# TMC2130.net
KiCad netlist of a schematic drawn in Altium Designer
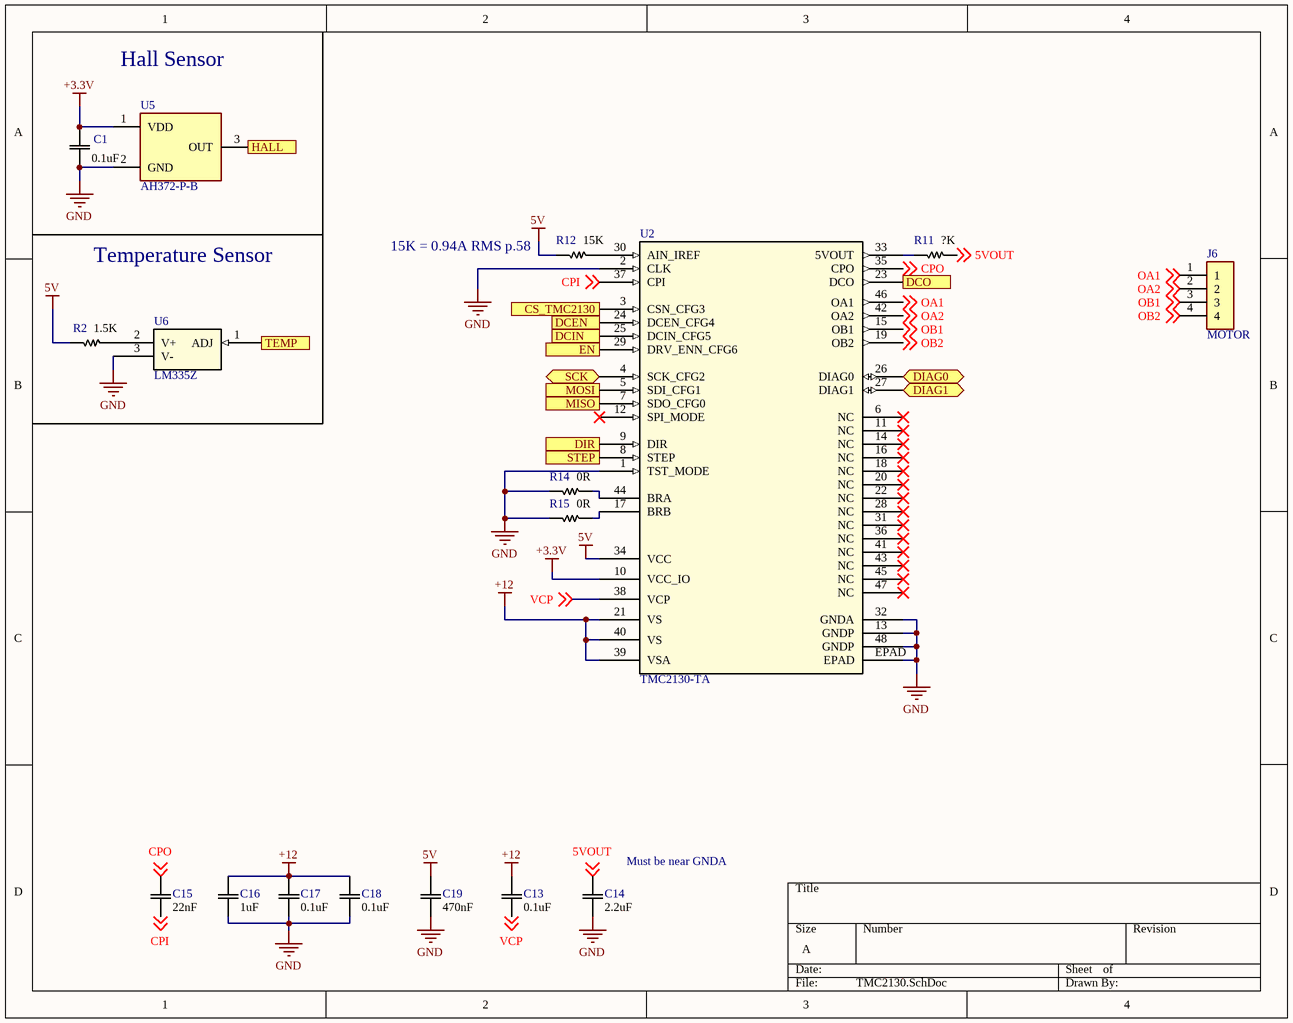
[diagram p0: TMC2130.SchDoc]

(export (version "E")
  (design (tool "Eeschema 10.0.6"))
  (components
    (comp (ref "C1")
      (value "0.1uF")
      (footprint "0603")
      (description "Capacitor SMD 1206")
      (fields
        (field (name "MANUFACTURER_PART_NUMBER") "12065A820JAT2A")
        (field (name "Comment") "Capacitor 1206")
        (field (name "COPYRIGHT") "Copyright (C) 2018 Accelerated Designs. All rights reserved")
      )
      (libsource (lib "Schematic_Emile") (part "Capacitor 1206"))
    )
    (comp (ref "C13")
      (value "0.1uF")
      (footprint "0603")
      (description "Capacitor SMD 1206")
      (fields
        (field (name "MANUFACTURER_PART_NUMBER") "12065A820JAT2A")
        (field (name "Comment") "Capacitor 1206")
        (field (name "COPYRIGHT") "Copyright (C) 2018 Accelerated Designs. All rights reserved")
      )
      (libsource (lib "Schematic_Emile") (part "Capacitor 1206"))
    )
    (comp (ref "C14")
      (value "2.2uF")
      (footprint "0603")
      (description "Capacitor SMD 1206")
      (fields
        (field (name "MANUFACTURER_PART_NUMBER") "12065A820JAT2A")
        (field (name "Comment") "Capacitor 1206")
        (field (name "COPYRIGHT") "Copyright (C) 2018 Accelerated Designs. All rights reserved")
      )
      (libsource (lib "Schematic_Emile") (part "Capacitor 1206"))
    )
    (comp (ref "C15")
      (value "22nF")
      (footprint "0603")
      (description "Capacitor SMD 1206")
      (fields
        (field (name "MANUFACTURER_PART_NUMBER") "12065A820JAT2A")
        (field (name "Comment") "Capacitor 1206")
        (field (name "COPYRIGHT") "Copyright (C) 2018 Accelerated Designs. All rights reserved")
      )
      (libsource (lib "Schematic_Emile") (part "Capacitor 1206"))
    )
    (comp (ref "C16")
      (value "1uF")
      (footprint "0603")
      (description "Capacitor SMD 1206")
      (fields
        (field (name "MANUFACTURER_PART_NUMBER") "12065A820JAT2A")
        (field (name "Comment") "Capacitor 1206")
        (field (name "COPYRIGHT") "Copyright (C) 2018 Accelerated Designs. All rights reserved")
      )
      (libsource (lib "Schematic_Emile") (part "Capacitor 1206"))
    )
    (comp (ref "C17")
      (value "0.1uF")
      (footprint "0603")
      (description "Capacitor SMD 1206")
      (fields
        (field (name "MANUFACTURER_PART_NUMBER") "12065A820JAT2A")
        (field (name "Comment") "Capacitor 1206")
        (field (name "COPYRIGHT") "Copyright (C) 2018 Accelerated Designs. All rights reserved")
      )
      (libsource (lib "Schematic_Emile") (part "Capacitor 1206"))
    )
    (comp (ref "C18")
      (value "0.1uF")
      (footprint "0603")
      (description "Capacitor SMD 1206")
      (fields
        (field (name "MANUFACTURER_PART_NUMBER") "12065A820JAT2A")
        (field (name "Comment") "Capacitor 1206")
        (field (name "COPYRIGHT") "Copyright (C) 2018 Accelerated Designs. All rights reserved")
      )
      (libsource (lib "Schematic_Emile") (part "Capacitor 1206"))
    )
    (comp (ref "C19")
      (value "470nF")
      (footprint "0603")
      (description "Capacitor SMD 1206")
      (fields
        (field (name "MANUFACTURER_PART_NUMBER") "12065A820JAT2A")
        (field (name "Comment") "Capacitor 1206")
        (field (name "COPYRIGHT") "Copyright (C) 2018 Accelerated Designs. All rights reserved")
      )
      (libsource (lib "Schematic_Emile") (part "Capacitor 1206"))
    )
    (comp (ref "J6")
      (value "MOTOR")
      (footprint "JST 4POS 2.5mm 90°")
      (description "Connector")
      (fields
        (field (name "MANUFACTURER_PART_NUMBER") "S4B-XH-A(LF)(SN)")
        (field (name "RS PART NUMBER") "8201589P")
      )
      (libsource (lib "Schematic_Emile") (part "JST 4POS"))
    )
    (comp (ref "R2")
      (value "1.5K")
      (footprint "0603")
      (description "Resistor 1206 SMD")
      (fields
        (field (name "MANUFACTURER_PART_NUMBER") "ERJ8CWFR024V")
        (field (name "Comment") "Resistor 1206")
        (field (name "COPYRIGHT") "Copyright (C) 2018 Accelerated Designs. All rights reserved")
      )
      (libsource (lib "Schematic_Emile") (part "Resistor 1206"))
    )
    (comp (ref "R11")
      (value "?K")
      (footprint "0603")
      (description "Resistor 0603 SMD")
      (fields
        (field (name "MANUFACTURER_PART_NUMBER") "ERJ8CWFR024V")
        (field (name "Comment") "Resistor 0603")
        (field (name "COPYRIGHT") "Copyright (C) 2018 Accelerated Designs. All rights reserved")
      )
      (libsource (lib "Schematic_Emile") (part "Resistor 1206"))
    )
    (comp (ref "R12")
      (value "15K")
      (footprint "0603")
      (description "Resistor 0603 SMD")
      (fields
        (field (name "MANUFACTURER_PART_NUMBER") "ERJ8CWFR024V")
        (field (name "Comment") "Resistor 0603")
        (field (name "COPYRIGHT") "Copyright (C) 2018 Accelerated Designs. All rights reserved")
      )
      (libsource (lib "Schematic_Emile") (part "Resistor 1206"))
    )
    (comp (ref "R14")
      (value "0R")
      (footprint "0603")
      (description "Resistor 0603 SMD")
      (fields
        (field (name "MANUFACTURER_PART_NUMBER") "ERJ8CWFR024V")
        (field (name "Comment") "Resistor 0603")
        (field (name "COPYRIGHT") "Copyright (C) 2018 Accelerated Designs. All rights reserved")
      )
      (libsource (lib "Schematic_Emile") (part "Resistor 1206"))
    )
    (comp (ref "R15")
      (value "0R")
      (footprint "0603")
      (description "Resistor 0603 SMD")
      (fields
        (field (name "MANUFACTURER_PART_NUMBER") "ERJ8CWFR024V")
        (field (name "Comment") "Resistor 0603")
        (field (name "COPYRIGHT") "Copyright (C) 2018 Accelerated Designs. All rights reserved")
      )
      (libsource (lib "Schematic_Emile") (part "Resistor 1206"))
    )
    (comp (ref "U2")
      (value "TMC2130-TA")
      (footprint "eTQFP48_9x9")
      (description "Motor Driver TMC2130")
      (fields (field (name "COPYRIGHT") "Copyright (C) 2016 Accelerated Designs. All rights reserved"))
      (libsource (lib "Schematic_Emile") (part "TMC2130-TA"))
    )
    (comp (ref "U5")
      (value "AH372-P-B")
      (footprint "Footprint_Emile:AH372PB")
      (description "Hall Sensor")
      (fields (field (name "MOUSER PART NUMBER") "621-AH372-P-B") (field (name "RS PART NUMBER") "1333361P"))
      (libsource (lib "Schematic_Emile") (part "AH372-P-B"))
    )
    (comp (ref "U6")
      (value "LM335Z")
      (footprint "TO92")
      (description "Temperature Sensor")
      (fields (field (name "COPYRIGHT") "Copyright (C) 2018 Accelerated Designs. All rights reserved"))
      (libsource (lib "Schematic_Emile") (part "LM335Z"))
    )
  )
  (nets
    (net (code "1") (name "+3.3V") (class "Default")
      (node (ref "C1") (pin "2") (pinfunction "2_2") (pintype "passive"))
      (node (ref "U2") (pin "10") (pinfunction "VCC_IO_10") (pintype "power_in"))
      (node (ref "U5") (pin "1") (pinfunction "VDD_1") (pintype "passive"))
    )
    (net (code "2") (name "+12") (class "Default")
      (node (ref "C13") (pin "2") (pinfunction "2_2") (pintype "passive"))
      (node (ref "C16") (pin "2") (pinfunction "2_2") (pintype "passive"))
      (node (ref "C17") (pin "2") (pinfunction "2_2") (pintype "passive"))
      (node (ref "C18") (pin "2") (pinfunction "2_2") (pintype "passive"))
      (node (ref "U2") (pin "21") (pinfunction "VS_21") (pintype "power_in"))
      (node (ref "U2") (pin "39") (pinfunction "VSA_39") (pintype "power_in"))
      (node (ref "U2") (pin "40") (pinfunction "VS_40") (pintype "power_in"))
    )
    (net (code "3") (name "/CS_TMC2130") (class "Default")
      (node (ref "U2") (pin "3") (pinfunction "CSN_CFG3_3") (pintype "input"))
    )
    (net (code "4") (name "/DCEN") (class "Default")
      (node (ref "U2") (pin "24") (pinfunction "DCEN_CFG4_24") (pintype "input"))
    )
    (net (code "5") (name "/DCIN") (class "Default")
      (node (ref "U2") (pin "25") (pinfunction "DCIN_CFG5_25") (pintype "input"))
    )
    (net (code "6") (name "/DCO") (class "Default")
      (node (ref "U2") (pin "23") (pinfunction "DCO_23") (pintype "output"))
    )
    (net (code "7") (name "/DIAG0") (class "Default")
      (node (ref "U2") (pin "26") (pinfunction "DIAG0_26") (pintype "bidirectional"))
    )
    (net (code "8") (name "/DIAG1") (class "Default")
      (node (ref "U2") (pin "27") (pinfunction "DIAG1_27") (pintype "bidirectional"))
    )
    (net (code "9") (name "/DIR") (class "Default")
      (node (ref "U2") (pin "9") (pinfunction "DIR_9") (pintype "input"))
    )
    (net (code "10") (name "/EN") (class "Default")
      (node (ref "U2") (pin "29") (pinfunction "DRV_ENN_CFG6_29") (pintype "input"))
    )
    (net (code "11") (name "/HALL") (class "Default")
      (node (ref "U5") (pin "3") (pinfunction "OUT_3") (pintype "passive"))
    )
    (net (code "12") (name "/MISO") (class "Default")
      (node (ref "U2") (pin "7") (pinfunction "SDO_CFG0_7") (pintype "input"))
    )
    (net (code "13") (name "/MOSI") (class "Default")
      (node (ref "U2") (pin "5") (pinfunction "SDI_CFG1_5") (pintype "input"))
    )
    (net (code "14") (name "/SCK") (class "Default")
      (node (ref "U2") (pin "4") (pinfunction "SCK_CFG2_4") (pintype "input"))
    )
    (net (code "15") (name "/STEP") (class "Default")
      (node (ref "U2") (pin "8") (pinfunction "STEP_8") (pintype "input"))
    )
    (net (code "16") (name "/TEMP") (class "Default")
      (node (ref "U6") (pin "1") (pinfunction "ADJ_1") (pintype "input"))
    )
    (net (code "17") (name "5V") (class "Default")
      (node (ref "C19") (pin "2") (pinfunction "2_2") (pintype "passive"))
      (node (ref "R12") (pin "1") (pinfunction "1_1") (pintype "passive"))
      (node (ref "R2") (pin "1") (pinfunction "1_1") (pintype "passive"))
      (node (ref "U2") (pin "34") (pinfunction "VCC_34") (pintype "power_in"))
    )
    (net (code "18") (name "5VOUT") (class "Default")
      (node (ref "C14") (pin "2") (pinfunction "2_2") (pintype "passive"))
      (node (ref "R11") (pin "2") (pinfunction "2_2") (pintype "passive"))
    )
    (net (code "19") (name "CPI") (class "Default")
      (node (ref "C15") (pin "1") (pinfunction "1_1") (pintype "passive"))
      (node (ref "U2") (pin "37") (pinfunction "CPI_37") (pintype "input"))
    )
    (net (code "20") (name "CPO") (class "Default")
      (node (ref "C15") (pin "2") (pinfunction "2_2") (pintype "passive"))
      (node (ref "U2") (pin "35") (pinfunction "CPO_35") (pintype "output"))
    )
    (net (code "21") (name "GND") (class "Default")
      (node (ref "C1") (pin "1") (pinfunction "1_1") (pintype "passive"))
      (node (ref "C14") (pin "1") (pinfunction "1_1") (pintype "passive"))
      (node (ref "C16") (pin "1") (pinfunction "1_1") (pintype "passive"))
      (node (ref "C17") (pin "1") (pinfunction "1_1") (pintype "passive"))
      (node (ref "C18") (pin "1") (pinfunction "1_1") (pintype "passive"))
      (node (ref "C19") (pin "1") (pinfunction "1_1") (pintype "passive"))
      (node (ref "R14") (pin "1") (pinfunction "1_1") (pintype "passive"))
      (node (ref "R15") (pin "1") (pinfunction "1_1") (pintype "passive"))
      (node (ref "U2") (pin "1") (pinfunction "TST_MODE_1") (pintype "input"))
      (node (ref "U2") (pin "13") (pinfunction "GNDP_13") (pintype "power_in"))
      (node (ref "U2") (pin "2") (pinfunction "CLK_2") (pintype "input"))
      (node (ref "U2") (pin "32") (pinfunction "GNDA_32") (pintype "power_in"))
      (node (ref "U2") (pin "48") (pinfunction "GNDP_48") (pintype "power_in"))
      (node (ref "U2") (pin "EPAD") (pinfunction "EPAD_EPAD") (pintype "passive"))
      (node (ref "U5") (pin "2") (pinfunction "GND_2") (pintype "passive"))
      (node (ref "U6") (pin "3") (pinfunction "V-_3") (pintype "power_in"))
    )
    (net (code "22") (name "Net-(U2-5VOUT)") (class "Default")
      (node (ref "R11") (pin "1") (pinfunction "1_1") (pintype "passive"))
      (node (ref "U2") (pin "33") (pinfunction "5VOUT_33") (pintype "output"))
    )
    (net (code "23") (name "Net-(U2-AIN_IREF)") (class "Default")
      (node (ref "R12") (pin "2") (pinfunction "2_2") (pintype "passive"))
      (node (ref "U2") (pin "30") (pinfunction "AIN_IREF_30") (pintype "input"))
    )
    (net (code "24") (name "Net-(U2-BRA)") (class "Default")
      (node (ref "R14") (pin "2") (pinfunction "2_2") (pintype "passive"))
      (node (ref "U2") (pin "44") (pinfunction "BRA_44") (pintype "passive"))
    )
    (net (code "25") (name "Net-(U2-BRB)") (class "Default")
      (node (ref "R15") (pin "2") (pinfunction "2_2") (pintype "passive"))
      (node (ref "U2") (pin "17") (pinfunction "BRB_17") (pintype "passive"))
    )
    (net (code "26") (name "Net-(U6-V+)") (class "Default")
      (node (ref "R2") (pin "2") (pinfunction "2_2") (pintype "passive"))
      (node (ref "U6") (pin "2") (pinfunction "V+_2") (pintype "power_in"))
    )
    (net (code "27") (name "OA1") (class "Default")
      (node (ref "J6") (pin "1") (pinfunction "1_1") (pintype "passive"))
      (node (ref "U2") (pin "46") (pinfunction "OA1_46") (pintype "output"))
    )
    (net (code "28") (name "OA2") (class "Default")
      (node (ref "J6") (pin "2") (pinfunction "2_2") (pintype "passive"))
      (node (ref "U2") (pin "42") (pinfunction "OA2_42") (pintype "output"))
    )
    (net (code "29") (name "OB1") (class "Default")
      (node (ref "J6") (pin "3") (pinfunction "3_3") (pintype "passive"))
      (node (ref "U2") (pin "15") (pinfunction "OB1_15") (pintype "output"))
    )
    (net (code "30") (name "OB2") (class "Default")
      (node (ref "J6") (pin "4") (pinfunction "4_4") (pintype "passive"))
      (node (ref "U2") (pin "19") (pinfunction "OB2_19") (pintype "output"))
    )
    (net (code "31") (name "VCP") (class "Default")
      (node (ref "C13") (pin "1") (pinfunction "1_1") (pintype "passive"))
      (node (ref "U2") (pin "38") (pinfunction "VCP_38") (pintype "power_in"))
    )
    (net (code "32") (name "unconnected-(U2-NC-Pad6)") (class "Default")
      (node (ref "U2") (pin "6") (pinfunction "NC_6") (pintype "passive+no_connect"))
    )
    (net (code "33") (name "unconnected-(U2-NC-Pad11)") (class "Default")
      (node (ref "U2") (pin "11") (pinfunction "NC_11") (pintype "passive+no_connect"))
    )
    (net (code "34") (name "unconnected-(U2-NC-Pad14)") (class "Default")
      (node (ref "U2") (pin "14") (pinfunction "NC_14") (pintype "passive+no_connect"))
    )
    (net (code "35") (name "unconnected-(U2-NC-Pad16)") (class "Default")
      (node (ref "U2") (pin "16") (pinfunction "NC_16") (pintype "passive+no_connect"))
    )
    (net (code "36") (name "unconnected-(U2-NC-Pad18)") (class "Default")
      (node (ref "U2") (pin "18") (pinfunction "NC_18") (pintype "passive+no_connect"))
    )
    (net (code "37") (name "unconnected-(U2-NC-Pad20)") (class "Default")
      (node (ref "U2") (pin "20") (pinfunction "NC_20") (pintype "passive+no_connect"))
    )
    (net (code "38") (name "unconnected-(U2-NC-Pad22)") (class "Default")
      (node (ref "U2") (pin "22") (pinfunction "NC_22") (pintype "passive+no_connect"))
    )
    (net (code "39") (name "unconnected-(U2-NC-Pad28)") (class "Default")
      (node (ref "U2") (pin "28") (pinfunction "NC_28") (pintype "passive+no_connect"))
    )
    (net (code "40") (name "unconnected-(U2-NC-Pad31)") (class "Default")
      (node (ref "U2") (pin "31") (pinfunction "NC_31") (pintype "passive+no_connect"))
    )
    (net (code "41") (name "unconnected-(U2-NC-Pad36)") (class "Default")
      (node (ref "U2") (pin "36") (pinfunction "NC_36") (pintype "passive+no_connect"))
    )
    (net (code "42") (name "unconnected-(U2-NC-Pad41)") (class "Default")
      (node (ref "U2") (pin "41") (pinfunction "NC_41") (pintype "passive+no_connect"))
    )
    (net (code "43") (name "unconnected-(U2-NC-Pad43)") (class "Default")
      (node (ref "U2") (pin "43") (pinfunction "NC_43") (pintype "passive+no_connect"))
    )
    (net (code "44") (name "unconnected-(U2-NC-Pad45)") (class "Default")
      (node (ref "U2") (pin "45") (pinfunction "NC_45") (pintype "passive+no_connect"))
    )
    (net (code "45") (name "unconnected-(U2-NC-Pad47)") (class "Default")
      (node (ref "U2") (pin "47") (pinfunction "NC_47") (pintype "passive+no_connect"))
    )
    (net (code "46") (name "unconnected-(U2-SPI_MODE-Pad12)") (class "Default")
      (node (ref "U2") (pin "12") (pinfunction "SPI_MODE_12") (pintype "input+no_connect"))
    )
  )
)
